# TopLevel.net
KiCad netlist of a schematic drawn in Altium Designer
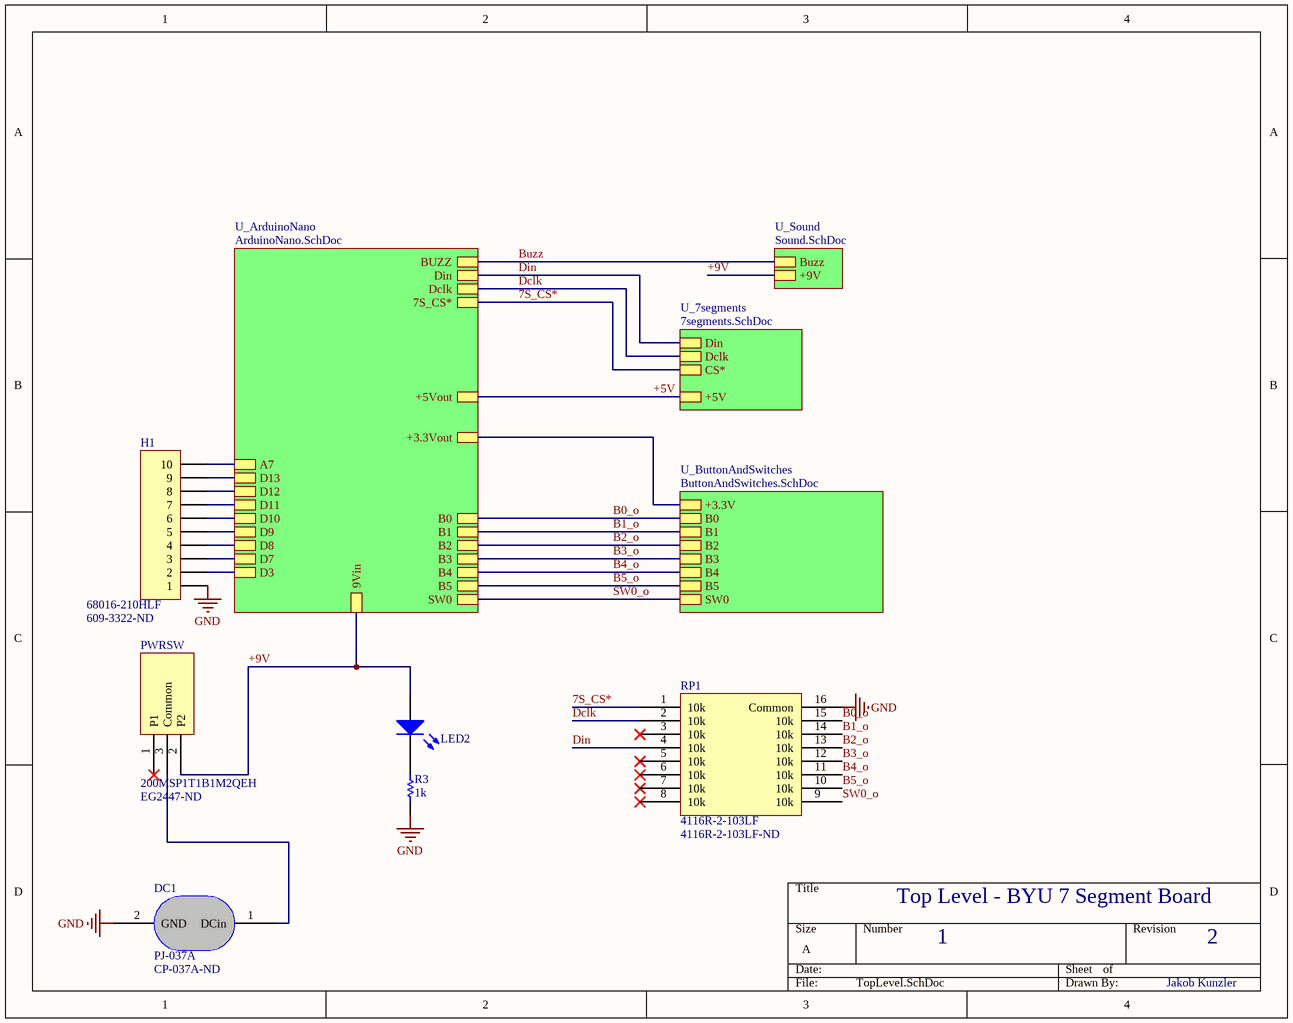
[diagram p0: TopLevel.SchDoc]

(export (version "E")
  (design (tool "Eeschema 10.0.6"))
  (components
    (comp (ref "DC1")
      (value "PJ-037A")
      (footprint "PJ-037A")
      (description "CONN PWR JACK 2X5.5MM SOLDER")
      (fields (field (name "SUPPLIER PART NUMBER 1") "CP-037A-ND"))
      (libsource (lib "BYU7SegBoard") (part "DCpowerBarrel"))
    )
    (comp (ref "H1")
      (value "68016-210HLF")
      (footprint "Header1X10")
      (description "Header 10 Right Angle 100 mil")
      (fields
        (field (name "SUPPLIER PART NUMBER 1") "609-3322-ND")
        (field (name "PUBLISHER") "Altium Limited")
      )
      (libsource (lib "BYU7SegBoard") (part "Header 10 Right Angle 100 mil"))
    )
    (comp (ref "LED2")
      (value "LTL-4223")
      (footprint "LED Through")
      (description "2 V drop 10 mA Red")
      (libsource (lib "BYU7SegBoard") (part "LED_RED"))
    )
    (comp (ref "PWRSW")
      (value "200MSP1T1B1M2QEH")
      (footprint "200MSP1T1B1M2QEH")
      (description "SWITCH TOGGLE SPDT 3A 120V")
      (fields (field (name "SUPPLIER PART NUMBER 1") "EG2447-ND"))
      (libsource (lib "BYU7SegBoard") (part "PowerSwitch"))
    )
    (comp (ref "R3")
      (value "1k")
      (footprint "Resistor Through Hole")
      (description "CF14JT1K00")
      (libsource (lib "BYU7SegBoard") (part "Resistor_1k"))
    )
    (comp (ref "RP1")
      (value "4116R-2-103LF")
      (footprint "4100R")
      (fields (field (name "SUPPLIER PART NUMBER 1") "4116R-2-103LF-ND"))
      (libsource (lib "BYU7SegBoard") (part "ResistorPack15"))
    )
  )
  (nets
    (net (code "3") (name "/+9V") (class "Default")
      (node (ref "LED2") (pin "1") (pinfunction "A_1") (pintype "passive"))
      (node (ref "PWRSW") (pin "2") (pinfunction "P2_2") (pintype "passive"))
    )
    (net (code "4") (name "/7S_CS*") (class "Default")
      (node (ref "RP1") (pin "1") (pinfunction "10k_1") (pintype "passive"))
    )
    (net (code "5") (name "/A7") (class "Default")
      (node (ref "H1") (pin "10") (pinfunction "10_10") (pintype "passive"))
    )
    (net (code "6") (name "/B0_o") (class "Default")
      (node (ref "RP1") (pin "15") (pinfunction "10k_15") (pintype "passive"))
    )
    (net (code "7") (name "/B1_o") (class "Default")
      (node (ref "RP1") (pin "14") (pinfunction "10k_14") (pintype "passive"))
    )
    (net (code "8") (name "/B2_o") (class "Default")
      (node (ref "RP1") (pin "13") (pinfunction "10k_13") (pintype "passive"))
    )
    (net (code "9") (name "/B3_o") (class "Default")
      (node (ref "RP1") (pin "12") (pinfunction "10k_12") (pintype "passive"))
    )
    (net (code "10") (name "/B4_o") (class "Default")
      (node (ref "RP1") (pin "11") (pinfunction "10k_11") (pintype "passive"))
    )
    (net (code "11") (name "/B5_o") (class "Default")
      (node (ref "RP1") (pin "10") (pinfunction "10k_10") (pintype "passive"))
    )
    (net (code "13") (name "/D3") (class "Default")
      (node (ref "H1") (pin "2") (pinfunction "2_2") (pintype "passive"))
    )
    (net (code "14") (name "/D7") (class "Default")
      (node (ref "H1") (pin "3") (pinfunction "3_3") (pintype "passive"))
    )
    (net (code "15") (name "/D8") (class "Default")
      (node (ref "H1") (pin "4") (pinfunction "4_4") (pintype "passive"))
    )
    (net (code "16") (name "/D9") (class "Default")
      (node (ref "H1") (pin "5") (pinfunction "5_5") (pintype "passive"))
    )
    (net (code "17") (name "/D10") (class "Default")
      (node (ref "H1") (pin "6") (pinfunction "6_6") (pintype "passive"))
    )
    (net (code "18") (name "/D11") (class "Default")
      (node (ref "H1") (pin "7") (pinfunction "7_7") (pintype "passive"))
    )
    (net (code "19") (name "/D12") (class "Default")
      (node (ref "H1") (pin "8") (pinfunction "8_8") (pintype "passive"))
    )
    (net (code "20") (name "/D13") (class "Default")
      (node (ref "H1") (pin "9") (pinfunction "9_9") (pintype "passive"))
    )
    (net (code "21") (name "/Dclk") (class "Default")
      (node (ref "RP1") (pin "2") (pinfunction "10k_2") (pintype "passive"))
    )
    (net (code "22") (name "/Din") (class "Default")
      (node (ref "RP1") (pin "4") (pinfunction "10k_4") (pintype "passive"))
    )
    (net (code "23") (name "/SW0_o") (class "Default")
      (node (ref "RP1") (pin "9") (pinfunction "10k_9") (pintype "passive"))
    )
    (net (code "24") (name "GND") (class "Default")
      (node (ref "DC1") (pin "2") (pinfunction "GND_2") (pintype "passive"))
      (node (ref "H1") (pin "1") (pinfunction "1_1") (pintype "passive"))
      (node (ref "R3") (pin "2") (pinfunction "2_2") (pintype "passive"))
      (node (ref "RP1") (pin "16") (pinfunction "Common_16") (pintype "passive"))
    )
    (net (code "25") (name "Net-(DC1-DCin)") (class "Default")
      (node (ref "DC1") (pin "1") (pinfunction "DCin_1") (pintype "passive"))
      (node (ref "PWRSW") (pin "3") (pinfunction "Common_3") (pintype "passive"))
    )
    (net (code "26") (name "Net-(LED2-K)") (class "Default")
      (node (ref "LED2") (pin "2") (pinfunction "K_2") (pintype "passive"))
      (node (ref "R3") (pin "1") (pinfunction "1_1") (pintype "passive"))
    )
    (net (code "27") (name "unconnected-(PWRSW-P1-Pad1)") (class "Default")
      (node (ref "PWRSW") (pin "1") (pinfunction "P1_1") (pintype "passive+no_connect"))
    )
    (net (code "28") (name "unconnected-(RP1-10k-Pad3)") (class "Default")
      (node (ref "RP1") (pin "3") (pinfunction "10k_3") (pintype "passive+no_connect"))
    )
    (net (code "29") (name "unconnected-(RP1-10k-Pad5)") (class "Default")
      (node (ref "RP1") (pin "5") (pinfunction "10k_5") (pintype "passive+no_connect"))
    )
    (net (code "30") (name "unconnected-(RP1-10k-Pad6)") (class "Default")
      (node (ref "RP1") (pin "6") (pinfunction "10k_6") (pintype "passive+no_connect"))
    )
    (net (code "31") (name "unconnected-(RP1-10k-Pad7)") (class "Default")
      (node (ref "RP1") (pin "7") (pinfunction "10k_7") (pintype "passive+no_connect"))
    )
    (net (code "32") (name "unconnected-(RP1-10k-Pad8)") (class "Default")
      (node (ref "RP1") (pin "8") (pinfunction "10k_8") (pintype "passive+no_connect"))
    )
  )
)
